# BQ24072-BREAKOUT.net
KiCad netlist of a schematic drawn in Altium Designer
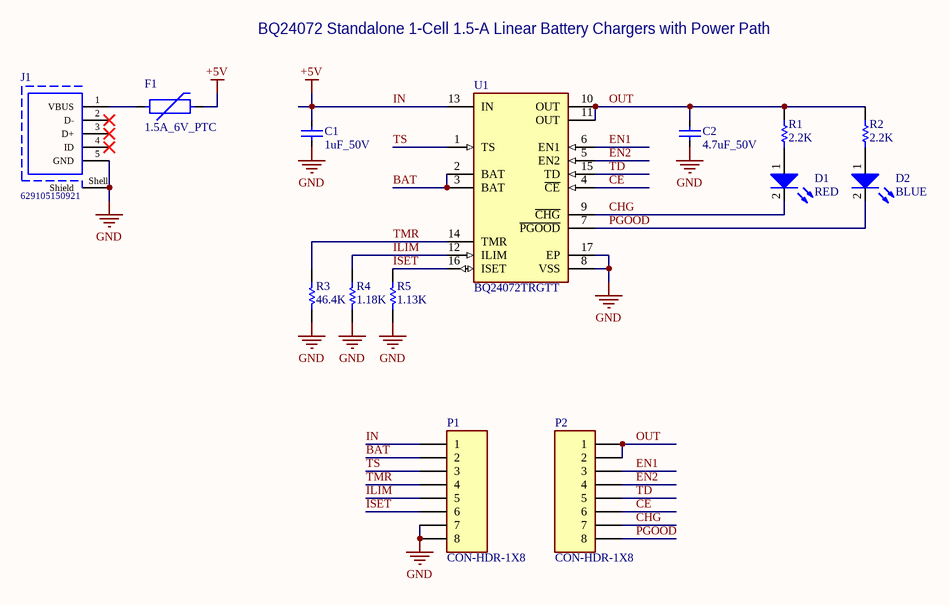
[diagram p0: BQ24072-BREAKOUT.SchDoc]

(export (version "E")
  (design (tool "Eeschema 10.0.6"))
  (components
    (comp (ref "C1")
      (value "1uF_50V")
      (footprint "CustomLib-Package:C0805")
      (description "C0805 0.10 μF X7R 30ppm/°C 10.00% 50 V")
      (fields
        (field (name "MANUFACTURER") "KEMET")
        (field (name "MANUFACTURER PART NUMBER") "C0805C104K5RAC7411")
      )
      (libsource (lib "CustomLib-Package") (part "CAPACITOR"))
    )
    (comp (ref "C2")
      (value "4.7uF_50V")
      (footprint "CustomLib-Package:C0805")
      (description "C0805 0.10 μF X7R 30ppm/°C 10.00% 50 V")
      (fields
        (field (name "MANUFACTURER") "KEMET")
        (field (name "MANUFACTURER PART NUMBER") "C0805C104K5RAC7411")
      )
      (libsource (lib "CustomLib-Package") (part "CAPACITOR"))
    )
    (comp (ref "D1")
      (value "RED")
      (footprint "LED0805")
      (description "Typical LED")
      (libsource (lib "CustomLib-Package") (part "LED"))
    )
    (comp (ref "D2")
      (value "BLUE")
      (footprint "LED0805")
      (description "Typical LED")
      (libsource (lib "CustomLib-Package") (part "LED"))
    )
    (comp (ref "F1")
      (value "1.5A_6V_PTC")
      (footprint "CustomLib-Package:R1206")
      (description "FUSE PPTC 1.5A (1206) 6V RESETTABLE")
      (fields (field (name "Comment") "NANOSMDC150F"))
      (libsource (lib "CustomLib-Package") (part "FUSE-PTC"))
    )
    (comp (ref "J1")
      (value "629105150921")
      (footprint "CON-MICRO-USB-B-SMD-WITH-HOLDER")
      (description "Micro USB 2.0 Type AB Receptacle WR-COM, Horizontal, SMT")
      (fields (field (name "MANUFACTURER") "Wurth Elektronik") (field (name "PUBLISHER") "WurthElektronik"))
      (libsource (lib "CustomLib-Package") (part "CON-MICRO-USB-AB-RCPT-SMD"))
    )
    (comp (ref "P1")
      (value "CON-HDR-1X8")
      (footprint "CON-HDR-1X8-2.54")
      (description "Pin Header, 8-Pin")
      (fields (field (name "PUBLISHER") "Altium Limited"))
      (libsource (lib "CustomLib-Package") (part "CON-HDR-1X8"))
    )
    (comp (ref "P2")
      (value "CON-HDR-1X8")
      (footprint "CON-HDR-1X8-2.54")
      (description "Pin Header, 8-Pin")
      (fields (field (name "PUBLISHER") "Altium Limited"))
      (libsource (lib "") (part "CON-HDR-1X8_1"))
    )
    (comp (ref "R1")
      (value "2.2K")
      (footprint "CustomLib-Package:R0805")
      (description "RES SMD 10K OHM 1% 1/8W 0805")
      (fields (field (name "TOLERANCE") "1%") (field (name "Comment") "CRG0805F10K"))
      (libsource (lib "CustomLib-Package") (part "RESISTOR"))
    )
    (comp (ref "R2")
      (value "2.2K")
      (footprint "CustomLib-Package:R0805")
      (description "RES SMD 10K OHM 1% 1/8W 0805")
      (fields (field (name "TOLERANCE") "1%") (field (name "Comment") "CRG0805F10K"))
      (libsource (lib "CustomLib-Package") (part "RESISTOR"))
    )
    (comp (ref "R3")
      (value "46.4K")
      (footprint "R0805")
      (description "RES SMD 10K OHM 1% 1/8W 0805")
      (fields (field (name "TOLERANCE") "1%") (field (name "Comment") "CRG0805F10K"))
      (libsource (lib "CustomLib-Package") (part "RESISTOR"))
    )
    (comp (ref "R4")
      (value "1.18K")
      (footprint "R0805")
      (description "RES SMD 10K OHM 1% 1/8W 0805")
      (fields (field (name "TOLERANCE") "1%") (field (name "Comment") "CRG0805F10K"))
      (libsource (lib "CustomLib-Package") (part "RESISTOR"))
    )
    (comp (ref "R5")
      (value "1.13K")
      (footprint "R0805")
      (description "RES SMD 10K OHM 1% 1/8W 0805")
      (fields (field (name "TOLERANCE") "1%") (field (name "Comment") "CRG0805F10K"))
      (libsource (lib "CustomLib-Package") (part "RESISTOR"))
    )
    (comp (ref "U1")
      (value "BQ24072TRGTT")
      (footprint "VQFN-16")
      (fields (field (name "MANUFACTURER") "Texas Instruments"))
      (libsource (lib "CustomLib-Package") (part "BQ24072"))
    )
  )
  (nets
    (net (code "1") (name "+5V") (class "Default")
      (node (ref "C1") (pin "1") (pinfunction "1_1") (pintype "passive"))
      (node (ref "F1") (pin "2") (pinfunction "2_2") (pintype "passive"))
      (node (ref "P1") (pin "1") (pinfunction "1_1") (pintype "passive"))
      (node (ref "U1") (pin "13") (pinfunction "IN_13") (pintype "power_in"))
    )
    (net (code "2") (name "/BAT") (class "Default")
      (node (ref "P1") (pin "2") (pinfunction "2_2") (pintype "passive"))
      (node (ref "U1") (pin "2") (pinfunction "BAT_2") (pintype "power_in"))
      (node (ref "U1") (pin "3") (pinfunction "BAT_3") (pintype "power_in"))
    )
    (net (code "3") (name "/CE") (class "Default")
      (node (ref "P2") (pin "6") (pinfunction "6_6") (pintype "passive"))
      (node (ref "U1") (pin "4") (pinfunction "~{CE}_4") (pintype "input"))
    )
    (net (code "4") (name "/CHG") (class "Default")
      (node (ref "D1") (pin "2") (pinfunction "K_2") (pintype "passive"))
      (node (ref "P2") (pin "7") (pinfunction "7_7") (pintype "passive"))
      (node (ref "U1") (pin "9") (pinfunction "~{CHG}_9") (pintype "tri_state"))
    )
    (net (code "5") (name "/EN1") (class "Default")
      (node (ref "P2") (pin "3") (pinfunction "3_3") (pintype "passive"))
      (node (ref "U1") (pin "6") (pinfunction "EN1_6") (pintype "input"))
    )
    (net (code "6") (name "/EN2") (class "Default")
      (node (ref "P2") (pin "4") (pinfunction "4_4") (pintype "passive"))
      (node (ref "U1") (pin "5") (pinfunction "EN2_5") (pintype "input"))
    )
    (net (code "7") (name "/ILIM") (class "Default")
      (node (ref "P1") (pin "5") (pinfunction "5_5") (pintype "passive"))
      (node (ref "R4") (pin "2") (pinfunction "2_2") (pintype "passive"))
      (node (ref "U1") (pin "12") (pinfunction "ILIM_12") (pintype "input"))
    )
    (net (code "8") (name "/ISET") (class "Default")
      (node (ref "P1") (pin "6") (pinfunction "6_6") (pintype "passive"))
      (node (ref "R5") (pin "2") (pinfunction "2_2") (pintype "passive"))
      (node (ref "U1") (pin "16") (pinfunction "ISET_16") (pintype "bidirectional"))
    )
    (net (code "9") (name "/OUT") (class "Default")
      (node (ref "C2") (pin "1") (pinfunction "1_1") (pintype "passive"))
      (node (ref "P2") (pin "1") (pinfunction "1_1") (pintype "passive"))
      (node (ref "P2") (pin "2") (pinfunction "2_2") (pintype "passive"))
      (node (ref "R1") (pin "1") (pinfunction "1_1") (pintype "passive"))
      (node (ref "R2") (pin "1") (pinfunction "1_1") (pintype "passive"))
      (node (ref "U1") (pin "10") (pinfunction "OUT_10") (pintype "power_in"))
      (node (ref "U1") (pin "11") (pinfunction "OUT_11") (pintype "power_in"))
    )
    (net (code "10") (name "/PGOOD") (class "Default")
      (node (ref "D2") (pin "2") (pinfunction "K_2") (pintype "passive"))
      (node (ref "P2") (pin "8") (pinfunction "8_8") (pintype "passive"))
      (node (ref "U1") (pin "7") (pinfunction "~{PGOOD}_7") (pintype "tri_state"))
    )
    (net (code "11") (name "/TD") (class "Default")
      (node (ref "P2") (pin "5") (pinfunction "5_5") (pintype "passive"))
      (node (ref "U1") (pin "15") (pinfunction "TD_15") (pintype "input"))
    )
    (net (code "12") (name "/TMR") (class "Default")
      (node (ref "P1") (pin "4") (pinfunction "4_4") (pintype "passive"))
      (node (ref "R3") (pin "2") (pinfunction "2_2") (pintype "passive"))
      (node (ref "U1") (pin "14") (pinfunction "TMR_14") (pintype "passive"))
    )
    (net (code "13") (name "/TS") (class "Default")
      (node (ref "P1") (pin "3") (pinfunction "3_3") (pintype "passive"))
      (node (ref "U1") (pin "1") (pinfunction "TS_1") (pintype "input"))
    )
    (net (code "14") (name "GND") (class "Default")
      (node (ref "C1") (pin "2") (pinfunction "2_2") (pintype "passive"))
      (node (ref "C2") (pin "2") (pinfunction "2_2") (pintype "passive"))
      (node (ref "J1") (pin "5") (pinfunction "GND_5") (pintype "passive"))
      (node (ref "J1") (pin "Shell") (pinfunction "Shield_Shell") (pintype "passive"))
      (node (ref "P1") (pin "7") (pinfunction "7_7") (pintype "passive"))
      (node (ref "P1") (pin "8") (pinfunction "8_8") (pintype "passive"))
      (node (ref "R3") (pin "1") (pinfunction "1_1") (pintype "passive"))
      (node (ref "R4") (pin "1") (pinfunction "1_1") (pintype "passive"))
      (node (ref "R5") (pin "1") (pinfunction "1_1") (pintype "passive"))
      (node (ref "U1") (pin "17") (pinfunction "EP_17") (pintype "power_in"))
      (node (ref "U1") (pin "8") (pinfunction "VSS_8") (pintype "power_in"))
    )
    (net (code "15") (name "Net-(D1-A)") (class "Default")
      (node (ref "D1") (pin "1") (pinfunction "A_1") (pintype "passive"))
      (node (ref "R1") (pin "2") (pinfunction "2_2") (pintype "passive"))
    )
    (net (code "16") (name "Net-(D2-A)") (class "Default")
      (node (ref "D2") (pin "1") (pinfunction "A_1") (pintype "passive"))
      (node (ref "R2") (pin "2") (pinfunction "2_2") (pintype "passive"))
    )
    (net (code "17") (name "Net-(J1-VBUS)") (class "Default")
      (node (ref "F1") (pin "1") (pinfunction "1_1") (pintype "passive"))
      (node (ref "J1") (pin "1") (pinfunction "VBUS_1") (pintype "passive"))
    )
    (net (code "18") (name "unconnected-(J1-D+-Pad3)") (class "Default")
      (node (ref "J1") (pin "3") (pinfunction "D+_3") (pintype "passive+no_connect"))
    )
    (net (code "19") (name "unconnected-(J1-D--Pad2)") (class "Default")
      (node (ref "J1") (pin "2") (pinfunction "D-_2") (pintype "passive+no_connect"))
    )
    (net (code "20") (name "unconnected-(J1-ID-Pad4)") (class "Default")
      (node (ref "J1") (pin "4") (pinfunction "ID_4") (pintype "passive+no_connect"))
    )
  )
)
